# Power.net
KiCad netlist of a schematic drawn in Altium Designer
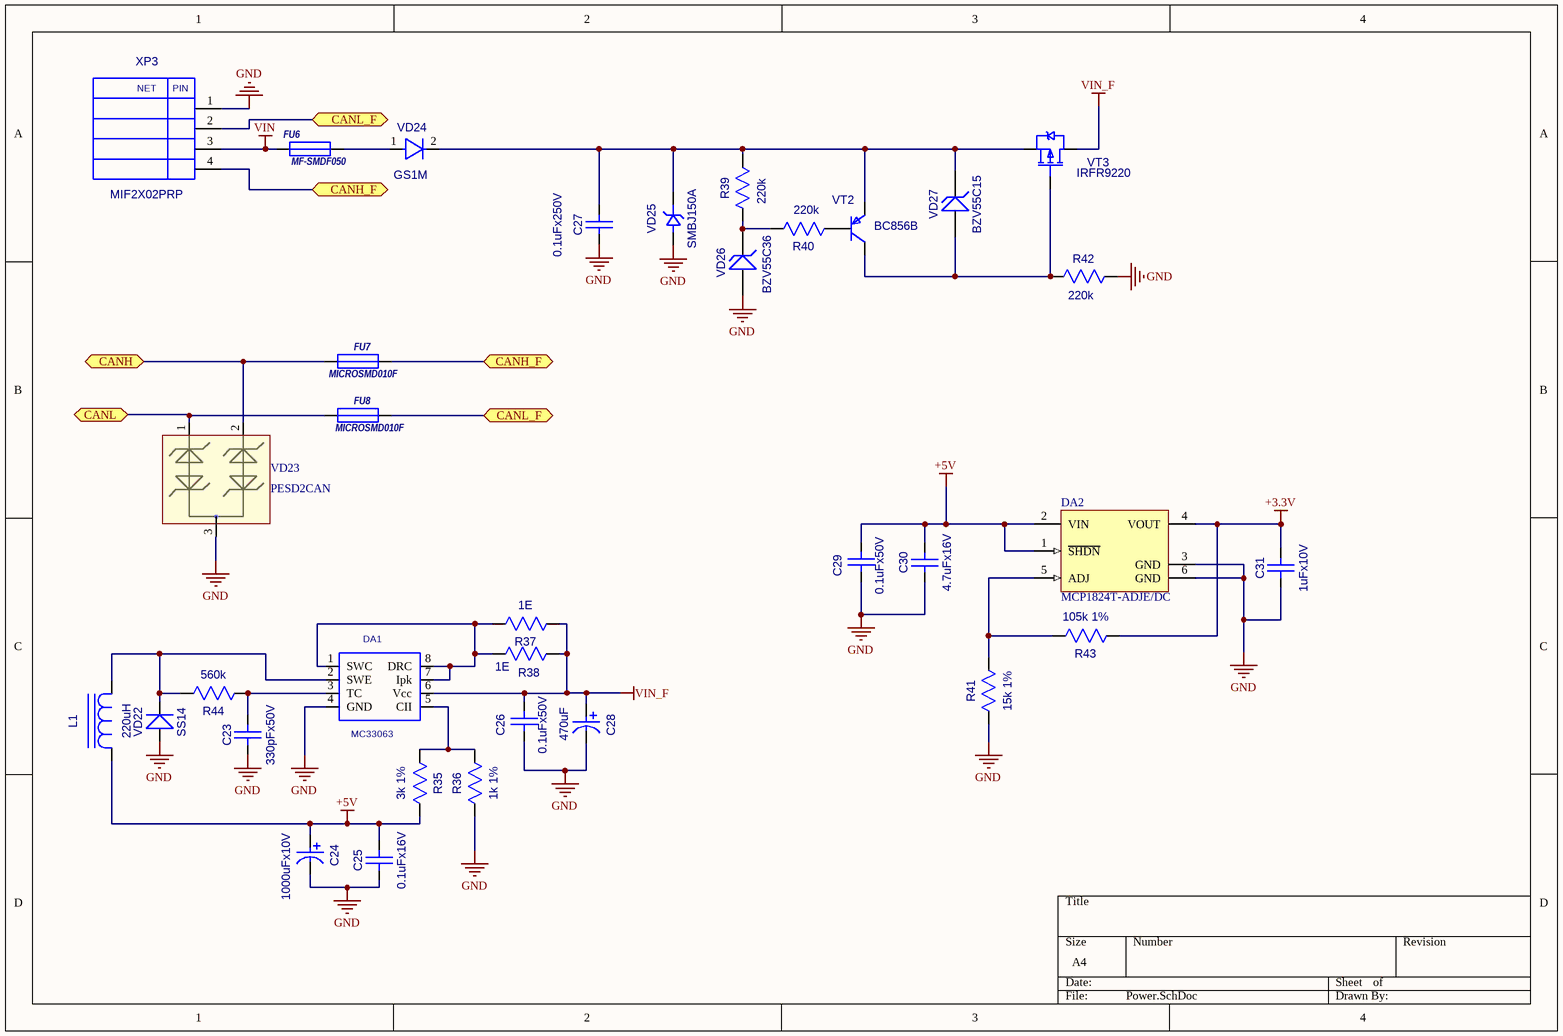
[diagram p0: Power.SchDoc]

(export (version "E")
  (design (tool "Eeschema 10.0.6"))
  (components
    (comp (ref "C23")
      (value "330pFx50V")
      (footprint "CC0603-3M")
      (description "CC0603")
      (libsource (lib "gprs_modem") (part "CC0603"))
    )
    (comp (ref "C24")
      (value "1000uFx10V")
      (footprint "CC8X3.5")
      (description "CAP0.35")
      (libsource (lib "gprs_modem") (part "CAP0.35"))
    )
    (comp (ref "C25")
      (value "0.1uFx16V")
      (footprint "CC0603-3M")
      (description "CC0603")
      (libsource (lib "gprs_modem") (part "CC0603"))
    )
    (comp (ref "C26")
      (value "0.1uFx50V")
      (footprint "CC0603-3M")
      (description "CC0603")
      (libsource (lib "gprs_modem") (part "CC0603"))
    )
    (comp (ref "C27")
      (value "0.1uFx250V")
      (footprint "CC1206-MIDI")
      (description "CC1206")
      (libsource (lib "gprs_modem") (part "CC1206"))
    )
    (comp (ref "C28")
      (value "470uF")
      (footprint "CC16X10_CAP0.5(1)(Primary)")
      (description "CAP0.5(1)")
      (libsource (lib "gprs_modem") (part "CAP0.5(1)"))
    )
    (comp (ref "C29")
      (value "0.1uFx50V")
      (footprint "CC0603-3M")
      (description "CC0603")
      (libsource (lib "gprs_modem") (part "CC0603"))
    )
    (comp (ref "C30")
      (value "4.7uFx16V")
      (footprint "CC0805-MIDI-2M1")
      (description "CC0805")
      (libsource (lib "gprs_modem") (part "CC0805"))
    )
    (comp (ref "C31")
      (value "1uFx10V")
      (footprint "CC0603-3M")
      (description "CC0603")
      (libsource (lib "gprs_modem") (part "CC0603"))
    )
    (comp (ref "DA1")
      (value "MC33063")
      (footprint "SO-8")
      (description "MC34063")
      (libsource (lib "Schetchik") (part "MC34063"))
    )
    (comp (ref "DA2")
      (value "MCP1824T-ADJE/DC")
      (footprint "SOT223-6")
      (fields (field (name "PUBLISHER") "Altium Limited"))
      (libsource (lib "gprs_modem") (part "MCP1824T-ADJE/DC"))
    )
    (comp (ref "FU6")
      (value "MF-SMDF050")
      (footprint "MF-SMDF")
      (description "MF-SMDF")
      (libsource (lib "gprs_modem") (part "MF-SMDF"))
    )
    (comp (ref "FU7")
      (value "MICROSMD010F")
      (footprint "RC1210")
      (description "MICROSMD")
      (libsource (lib "*") (part "MICROSMD"))
    )
    (comp (ref "FU8")
      (value "MICROSMD010F")
      (footprint "RC1210")
      (description "MICROSMD")
      (libsource (lib "*") (part "MICROSMD"))
    )
    (comp (ref "L1")
      (value "220uH")
      (footprint "SDR0805")
      (description "SDR0805")
      (libsource (lib "gprs_modem") (part "SDR0805"))
    )
    (comp (ref "R35")
      (value "3k 1%")
      (footprint "RC0603-3M")
      (description "RC0603")
      (libsource (lib "gprs_modem") (part "RC0603"))
    )
    (comp (ref "R36")
      (value "1k 1%")
      (footprint "RC0603-3M")
      (description "RC0603")
      (libsource (lib "gprs_modem") (part "RC0603"))
    )
    (comp (ref "R37")
      (value "1E")
      (footprint "RC0805_IPC_NOM")
      (description "RC0805")
      (libsource (lib "gprs_modem") (part "RC0805"))
    )
    (comp (ref "R38")
      (value "1E")
      (footprint "RC0805_IPC_NOM")
      (description "RC0805")
      (libsource (lib "gprs_modem") (part "RC0805"))
    )
    (comp (ref "R39")
      (value "220k")
      (footprint "RC1206-2M")
      (description "RC1206")
      (libsource (lib "gprs_modem") (part "RC1206"))
    )
    (comp (ref "R40")
      (value "220k")
      (footprint "RC1206-2M")
      (description "RC1206")
      (libsource (lib "gprs_modem") (part "RC1206"))
    )
    (comp (ref "R41")
      (value "15k 1%")
      (footprint "RC0603-3M")
      (description "RC0603")
      (libsource (lib "gprs_modem") (part "RC0603"))
    )
    (comp (ref "R42")
      (value "220k")
      (footprint "RC1206-2M")
      (description "RC1206")
      (libsource (lib "gprs_modem") (part "RC1206"))
    )
    (comp (ref "R43")
      (value "105k 1%")
      (footprint "RC0603-3M")
      (description "RC0603")
      (libsource (lib "gprs_modem") (part "RC0603"))
    )
    (comp (ref "R44")
      (value "560k")
      (footprint "RC0603-3M")
      (description "RC0603")
      (libsource (lib "gprs_modem") (part "RC0603"))
    )
    (comp (ref "VD22")
      (value "SS14")
      (footprint "SMA")
      (description "Schottky Rectifier")
      (libsource (lib "gprs_modem") (part "SS14"))
    )
    (comp (ref "VD23")
      (value "PESD2CAN")
      (footprint "SOT-23(123)")
      (description "TVS for CAN")
      (libsource (lib "gprs_modem") (part "PESD2CAN"))
    )
    (comp (ref "VD24") (value "GS1M") (footprint "SMA") (libsource (lib "Schetchik") (part "GS1M")))
    (comp (ref "VD25")
      (value "SMBJ150A")
      (footprint "SMB")
      (description "SMBJ")
      (libsource (lib "gprs_modem") (part "SMBJ"))
    )
    (comp (ref "VD26")
      (value "BZV55C36")
      (footprint "SOD-80")
      (description "Zener Voltage Regulator Diode")
      (libsource (lib "gprs_modem") (part "BZV55C12"))
    )
    (comp (ref "VD27")
      (value "BZV55C15")
      (footprint "SOD-80")
      (description "Zener Voltage Regulator Diode")
      (libsource (lib "gprs_modem") (part "BZV55C12"))
    )
    (comp (ref "VT2")
      (value "BC856B")
      (footprint "SOT-23(123)")
      (libsource (lib "Schetchik") (part "BC856B"))
    )
    (comp (ref "VT3")
      (value "IRFR9220")
      (footprint "D-PAK(TO-252AA)")
      (description "HEXFET Power MOSFET")
      (libsource (lib "gprs_modem") (part "IRFR9220"))
    )
    (comp (ref "XP3")
      (value "MIF2X02PRP")
      (footprint "MIF2X02PRP")
      (libsource (lib "Schetchik") (part "MIF2X02PRP"))
    )
  )
  (nets
    (net (code "1") (name "+3.3V") (class "Default")
      (node (ref "C31") (pin "2") (pinfunction "B_2") (pintype "passive"))
      (node (ref "DA2") (pin "4") (pinfunction "VOUT_4") (pintype "power_in"))
      (node (ref "R43") (pin "1") (pinfunction "A_1") (pintype "passive"))
    )
    (net (code "2") (name "+5V") (class "Default")
      (node (ref "C24") (pin "1") (pintype "passive"))
      (node (ref "C25") (pin "2") (pinfunction "B_2") (pintype "passive"))
      (node (ref "C29") (pin "1") (pinfunction "A_1") (pintype "passive"))
      (node (ref "C30") (pin "2") (pinfunction "B_2") (pintype "passive"))
      (node (ref "DA2") (pin "1") (pinfunction "~{SHDN}_1") (pintype "input"))
      (node (ref "DA2") (pin "2") (pinfunction "VIN_2") (pintype "power_in"))
      (node (ref "L1") (pin "1") (pinfunction "C_1") (pintype "passive"))
      (node (ref "R35") (pin "2") (pinfunction "B_2") (pintype "passive"))
    )
    (net (code "3") (name "/CANH") (class "Default")
      (node (ref "FU7") (pin "2") (pintype "passive"))
      (node (ref "VD23") (pin "2") (pinfunction "2_2") (pintype "passive"))
    )
    (net (code "4") (name "/CANH_F") (class "Default")
      (node (ref "FU7") (pin "1") (pintype "passive"))
      (node (ref "XP3") (pin "4") (pinfunction "4_4") (pintype "passive"))
    )
    (net (code "5") (name "/CANL") (class "Default")
      (node (ref "FU8") (pin "2") (pintype "passive"))
      (node (ref "VD23") (pin "1") (pinfunction "1_1") (pintype "passive"))
    )
    (net (code "6") (name "/CANL_F") (class "Default")
      (node (ref "FU8") (pin "1") (pintype "passive"))
      (node (ref "XP3") (pin "2") (pinfunction "2_2") (pintype "passive"))
    )
    (net (code "7") (name "GND") (class "Default")
      (node (ref "C23") (pin "1") (pinfunction "A_1") (pintype "passive"))
      (node (ref "C24") (pin "2") (pintype "passive"))
      (node (ref "C25") (pin "1") (pinfunction "A_1") (pintype "passive"))
      (node (ref "C26") (pin "2") (pinfunction "B_2") (pintype "passive"))
      (node (ref "C27") (pin "1") (pinfunction "A_1") (pintype "passive"))
      (node (ref "C28") (pin "1") (pintype "passive"))
      (node (ref "C29") (pin "2") (pinfunction "B_2") (pintype "passive"))
      (node (ref "C30") (pin "1") (pinfunction "A_1") (pintype "passive"))
      (node (ref "C31") (pin "1") (pinfunction "A_1") (pintype "passive"))
      (node (ref "DA1") (pin "4") (pinfunction "GND_4") (pintype "passive"))
      (node (ref "DA2") (pin "3") (pinfunction "GND_3") (pintype "power_in"))
      (node (ref "DA2") (pin "6") (pinfunction "GND_6") (pintype "power_in"))
      (node (ref "R36") (pin "1") (pinfunction "A_1") (pintype "passive"))
      (node (ref "R41") (pin "1") (pinfunction "A_1") (pintype "passive"))
      (node (ref "R42") (pin "2") (pinfunction "B_2") (pintype "passive"))
      (node (ref "VD22") (pin "1") (pinfunction "A_1") (pintype "passive"))
      (node (ref "VD23") (pin "3") (pinfunction "3_3") (pintype "passive"))
      (node (ref "VD25") (pin "1") (pinfunction "A_1") (pintype "passive"))
      (node (ref "VD26") (pin "1") (pinfunction "A_1") (pintype "passive"))
      (node (ref "XP3") (pin "1") (pinfunction "1_1") (pintype "passive"))
    )
    (net (code "8") (name "Net-(C23-B)") (class "Default")
      (node (ref "C23") (pin "2") (pinfunction "B_2") (pintype "passive"))
      (node (ref "DA1") (pin "3") (pinfunction "TC_3") (pintype "passive"))
      (node (ref "R44") (pin "1") (pinfunction "A_1") (pintype "passive"))
    )
    (net (code "9") (name "Net-(C27-B)") (class "Default")
      (node (ref "C27") (pin "2") (pinfunction "B_2") (pintype "passive"))
      (node (ref "R39") (pin "2") (pinfunction "B_2") (pintype "passive"))
      (node (ref "VD24") (pin "2") (pinfunction "K_2") (pintype "passive"))
      (node (ref "VD25") (pin "2") (pinfunction "K_2") (pintype "passive"))
      (node (ref "VD27") (pin "2") (pintype "passive"))
      (node (ref "VT2") (pin "2") (pinfunction "E_2") (pintype "passive"))
      (node (ref "VT3") (pin "2") (pinfunction "S_2") (pintype "passive"))
    )
    (net (code "10") (name "Net-(DA1-CII)") (class "Default")
      (node (ref "DA1") (pin "5") (pinfunction "CII_5") (pintype "passive"))
      (node (ref "R35") (pin "1") (pinfunction "A_1") (pintype "passive"))
      (node (ref "R36") (pin "2") (pinfunction "B_2") (pintype "passive"))
    )
    (net (code "11") (name "Net-(DA1-DRC)") (class "Default")
      (node (ref "DA1") (pin "1") (pinfunction "SWC_1") (pintype "passive"))
      (node (ref "DA1") (pin "7") (pinfunction "Ipk_7") (pintype "passive"))
      (node (ref "DA1") (pin "8") (pinfunction "DRC_8") (pintype "passive"))
      (node (ref "R37") (pin "2") (pinfunction "B_2") (pintype "passive"))
      (node (ref "R38") (pin "2") (pinfunction "B_2") (pintype "passive"))
    )
    (net (code "12") (name "Net-(DA1-SWE)") (class "Default")
      (node (ref "DA1") (pin "2") (pinfunction "SWE_2") (pintype "passive"))
      (node (ref "L1") (pin "2") (pinfunction "A_2") (pintype "passive"))
      (node (ref "R44") (pin "2") (pinfunction "B_2") (pintype "passive"))
      (node (ref "VD22") (pin "2") (pinfunction "K_2") (pintype "passive"))
    )
    (net (code "13") (name "Net-(DA2-ADJ)") (class "Default")
      (node (ref "DA2") (pin "5") (pinfunction "ADJ_5") (pintype "input"))
      (node (ref "R41") (pin "2") (pinfunction "B_2") (pintype "passive"))
      (node (ref "R43") (pin "2") (pinfunction "B_2") (pintype "passive"))
    )
    (net (code "14") (name "Net-(R39-A)") (class "Default")
      (node (ref "R39") (pin "1") (pinfunction "A_1") (pintype "passive"))
      (node (ref "R40") (pin "2") (pinfunction "B_2") (pintype "passive"))
      (node (ref "VD26") (pin "2") (pintype "passive"))
    )
    (net (code "15") (name "Net-(R40-A)") (class "Default")
      (node (ref "R40") (pin "1") (pinfunction "A_1") (pintype "passive"))
      (node (ref "VT2") (pin "1") (pinfunction "B_1") (pintype "passive"))
    )
    (net (code "16") (name "Net-(R42-A)") (class "Default")
      (node (ref "R42") (pin "1") (pinfunction "A_1") (pintype "passive"))
      (node (ref "VD27") (pin "1") (pinfunction "A_1") (pintype "passive"))
      (node (ref "VT2") (pin "3") (pinfunction "C_3") (pintype "passive"))
      (node (ref "VT3") (pin "1") (pinfunction "G_1") (pintype "passive"))
    )
    (net (code "17") (name "Net-(VD24-A)") (class "Default")
      (node (ref "FU6") (pin "2") (pintype "passive"))
      (node (ref "VD24") (pin "1") (pinfunction "A_1") (pintype "passive"))
    )
    (net (code "18") (name "VIN") (class "Default")
      (node (ref "FU6") (pin "1") (pintype "passive"))
      (node (ref "XP3") (pin "3") (pinfunction "3_3") (pintype "passive"))
    )
    (net (code "19") (name "VIN_F") (class "Default")
      (node (ref "C26") (pin "1") (pinfunction "A_1") (pintype "passive"))
      (node (ref "C28") (pin "2") (pintype "passive"))
      (node (ref "DA1") (pin "6") (pinfunction "Vcc_6") (pintype "passive"))
      (node (ref "R37") (pin "1") (pinfunction "A_1") (pintype "passive"))
      (node (ref "R38") (pin "1") (pinfunction "A_1") (pintype "passive"))
      (node (ref "VT3") (pin "3") (pinfunction "D_3") (pintype "passive"))
    )
  )
)
